# Ux.net
KiCad netlist of a schematic drawn in Altium Designer
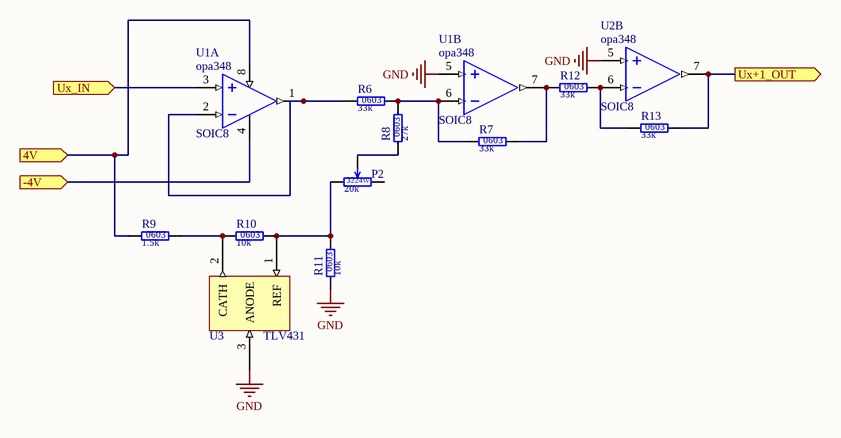
[diagram p0: Ux.SchDoc]

(export (version "E")
  (design (tool "Eeschema 10.0.6"))
  (components
    (comp (ref "P2")
      (value "20k")
      (footprint "Potentiometer")
      (fields (field (name "SCH_FOOTPRINT") "3224W") (field (name "Comment") "POT"))
      (libsource (lib "SIUE_Symbol") (part "POT"))
    )
    (comp (ref "R6")
      (value "R")
      (fields
        (field (name "TOLERANCE") "Value")
        (field (name "SCH_FOOTPRINT") "0603")
        (field (name "RESISTANCE") "33k")
      )
      (libsource (lib "SIUE_Symbol") (part "R"))
    )
    (comp (ref "R7")
      (value "R")
      (fields
        (field (name "TOLERANCE") "Value")
        (field (name "SCH_FOOTPRINT") "0603")
        (field (name "RESISTANCE") "33k")
      )
      (libsource (lib "SIUE_Symbol") (part "R"))
    )
    (comp (ref "R8")
      (value "R")
      (fields
        (field (name "TOLERANCE") "Value")
        (field (name "SCH_FOOTPRINT") "0603")
        (field (name "RESISTANCE") "27k")
      )
      (libsource (lib "SIUE_Symbol") (part "R"))
    )
    (comp (ref "R9")
      (value "R")
      (fields
        (field (name "TOLERANCE") "Value")
        (field (name "SCH_FOOTPRINT") "0603")
        (field (name "RESISTANCE") "1.5k")
      )
      (libsource (lib "SIUE_Symbol") (part "R"))
    )
    (comp (ref "R10")
      (value "R")
      (fields
        (field (name "TOLERANCE") "Value")
        (field (name "SCH_FOOTPRINT") "0603")
        (field (name "RESISTANCE") "10k")
      )
      (libsource (lib "SIUE_Symbol") (part "R"))
    )
    (comp (ref "R11")
      (value "R")
      (fields
        (field (name "TOLERANCE") "Value")
        (field (name "SCH_FOOTPRINT") "0603")
        (field (name "RESISTANCE") "10k")
      )
      (libsource (lib "SIUE_Symbol") (part "R"))
    )
    (comp (ref "R12")
      (value "R")
      (fields
        (field (name "TOLERANCE") "Value")
        (field (name "SCH_FOOTPRINT") "0603")
        (field (name "RESISTANCE") "33k")
      )
      (libsource (lib "SIUE_Symbol") (part "R"))
    )
    (comp (ref "R13")
      (value "R")
      (fields
        (field (name "TOLERANCE") "Value")
        (field (name "SCH_FOOTPRINT") "0603")
        (field (name "RESISTANCE") "33k")
      )
      (libsource (lib "SIUE_Symbol") (part "R"))
    )
    (comp (ref "U1")
      (value "opa348")
      (fields (field (name "SCH_FOOTPRINT") "SOIC8") (field (name "Comment") "A2_8PIN_TYPICAL"))
      (libsource (lib "SIUE_Symbol") (part "A2_8PIN_TYPICAL"))
    )
    (comp (ref "U2")
      (value "opa348")
      (fields (field (name "SCH_FOOTPRINT") "SOIC8") (field (name "Comment") "A2_8PIN_TYPICAL"))
      (libsource (lib "SIUE_Symbol") (part "A2_8PIN_TYPICAL"))
    )
    (comp (ref "U3") (value "TLV431") (footprint "SOT23") (libsource (lib "SIUE_Symbol") (part "TLV431")))
  )
  (nets
    (net (code "1") (name "/-4V") (class "Default")
      (node (ref "U1") (pin "4") (pinfunction "GND_4") (pintype "power_in"))
    )
    (net (code "2") (name "/4V") (class "Default")
      (node (ref "R9") (pin "1") (pinfunction "1_1") (pintype "passive"))
      (node (ref "U1") (pin "8") (pinfunction "VDD_8") (pintype "input"))
    )
    (net (code "3") (name "/Ux+1_OUT") (class "Default")
      (node (ref "R13") (pin "2") (pinfunction "2_2") (pintype "passive"))
      (node (ref "U2") (pin "7") (pinfunction "OUT2_7") (pintype "output"))
    )
    (net (code "4") (name "/Ux_IN") (class "Default")
      (node (ref "U1") (pin "3") (pinfunction "IN+1_3") (pintype "input"))
    )
    (net (code "5") (name "GND") (class "Default")
      (node (ref "R11") (pin "1") (pinfunction "1_1") (pintype "passive"))
      (node (ref "U1") (pin "5") (pinfunction "IN+2_5") (pintype "input"))
      (node (ref "U2") (pin "5") (pinfunction "IN+2_5") (pintype "input"))
      (node (ref "U3") (pin "3") (pinfunction "ANODE_3") (pintype "input"))
    )
    (net (code "6") (name "Net-(P2-Pad2)") (class "Default")
      (node (ref "P2") (pin "2") (pinfunction "2_2") (pintype "passive"))
      (node (ref "R8") (pin "1") (pinfunction "1_1") (pintype "passive"))
    )
    (net (code "7") (name "Net-(U1A-IN-1)") (class "Default")
      (node (ref "R6") (pin "1") (pinfunction "1_1") (pintype "passive"))
      (node (ref "U1") (pin "1") (pinfunction "OUT1_1") (pintype "output"))
      (node (ref "U1") (pin "2") (pinfunction "IN-1_2") (pintype "input"))
    )
    (net (code "8") (name "Net-(U1B-IN-2)") (class "Default")
      (node (ref "R6") (pin "2") (pinfunction "2_2") (pintype "passive"))
      (node (ref "R7") (pin "1") (pinfunction "1_1") (pintype "passive"))
      (node (ref "R8") (pin "2") (pinfunction "2_2") (pintype "passive"))
      (node (ref "U1") (pin "6") (pinfunction "IN-2_6") (pintype "input"))
    )
    (net (code "9") (name "Net-(U1B-OUT2)") (class "Default")
      (node (ref "R12") (pin "1") (pinfunction "1_1") (pintype "passive"))
      (node (ref "R7") (pin "2") (pinfunction "2_2") (pintype "passive"))
      (node (ref "U1") (pin "7") (pinfunction "OUT2_7") (pintype "output"))
    )
    (net (code "10") (name "Net-(U2B-IN-2)") (class "Default")
      (node (ref "R12") (pin "2") (pinfunction "2_2") (pintype "passive"))
      (node (ref "R13") (pin "1") (pinfunction "1_1") (pintype "passive"))
      (node (ref "U2") (pin "6") (pinfunction "IN-2_6") (pintype "input"))
    )
    (net (code "11") (name "Net-(U3-CATH)") (class "Default")
      (node (ref "R10") (pin "1") (pinfunction "1_1") (pintype "passive"))
      (node (ref "R9") (pin "2") (pinfunction "2_2") (pintype "passive"))
      (node (ref "U3") (pin "2") (pinfunction "CATH_2") (pintype "output"))
    )
    (net (code "12") (name "Net-(U3-REF)") (class "Default")
      (node (ref "P2") (pin "1") (pinfunction "1_1") (pintype "passive"))
      (node (ref "R10") (pin "2") (pinfunction "2_2") (pintype "passive"))
      (node (ref "R11") (pin "2") (pinfunction "2_2") (pintype "passive"))
      (node (ref "U3") (pin "1") (pinfunction "REF_1") (pintype "input"))
    )
    (net (code "13") (name "unconnected-(P2-Pad3)") (class "Default")
      (node (ref "P2") (pin "3") (pinfunction "3_3") (pintype "passive"))
    )
  )
)
